# RT-HOT.net
KiCad netlist of a schematic drawn in Altium Designer
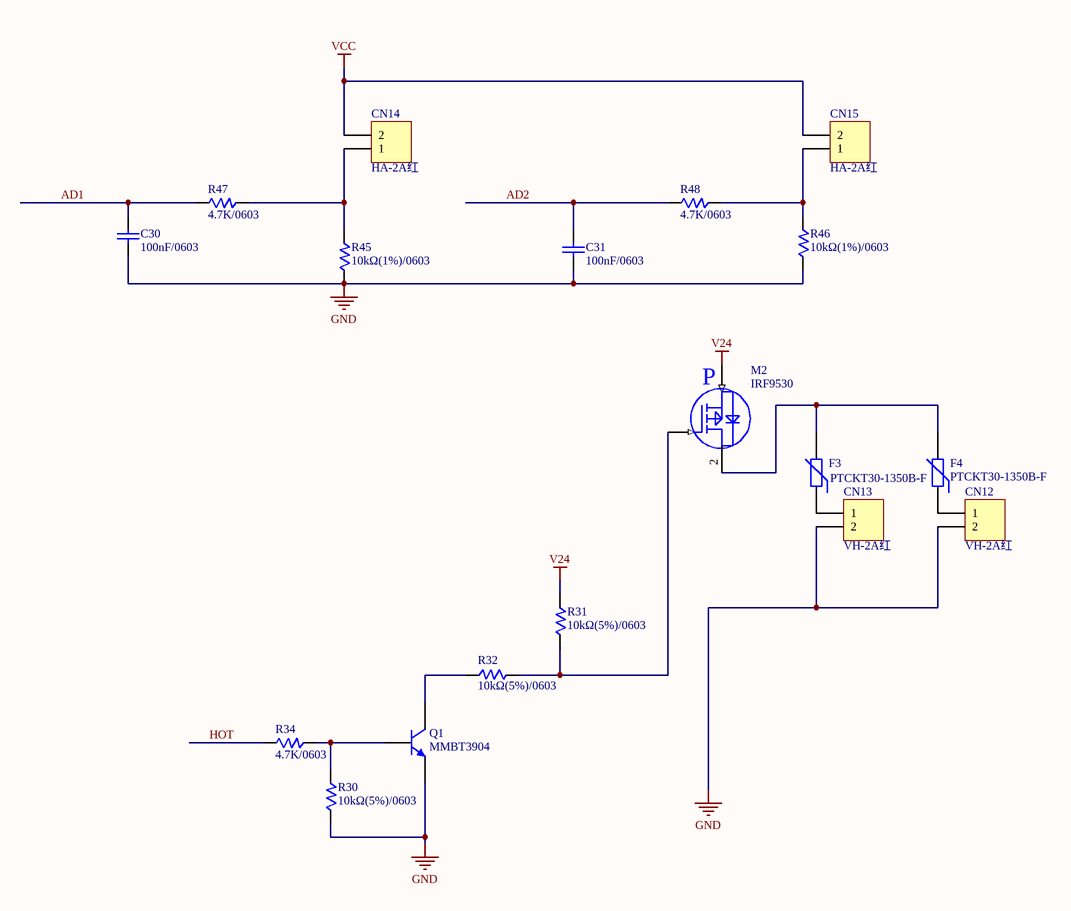
[diagram p0: RT-HOT.SchDoc]

(export (version "E")
  (design (tool "Eeschema 10.0.6"))
  (components
    (comp (ref "C30") (value "100nF/0603") (footprint "0603C") (libsource (lib "荣泰料号库") (part "C0603/100nF")))
    (comp (ref "C31") (value "100nF/0603") (footprint "0603C") (libsource (lib "荣泰料号库") (part "C0603/100nF")))
    (comp (ref "CN12")
      (value "VH-2A红")
      (footprint "CON-VH-2P")
      (libsource (lib "荣泰料号库") (part "CON-VH-2A(红色)"))
    )
    (comp (ref "CN13")
      (value "VH-2A红")
      (footprint "CON-VH-2P")
      (libsource (lib "荣泰料号库") (part "CON-VH-2A(红色)"))
    )
    (comp (ref "CN14")
      (value "HA-2A红")
      (footprint "CON-XA-2P")
      (libsource (lib "荣泰料号库") (part "CON-HA-2A(红色)"))
    )
    (comp (ref "CN15")
      (value "HA-2A红")
      (footprint "CON-XA-2P")
      (libsource (lib "荣泰料号库") (part "CON-HA-2A(红色)"))
    )
    (comp (ref "F3")
      (value "PTCKT30-1350B-F")
      (footprint "FRAD0.2")
      (libsource (lib "荣泰料号库") (part "F-PTCKT30-1350B-F/环保"))
    )
    (comp (ref "F4")
      (value "PTCKT30-1350B-F")
      (footprint "FRAD0.2")
      (libsource (lib "荣泰料号库") (part "F-PTCKT30-1350B-F/环保"))
    )
    (comp (ref "M2")
      (value "IRF9530")
      (footprint "TO-220AB")
      (libsource (lib "荣泰料号库") (part "MP-IRF9530/环保"))
    )
    (comp (ref "Q1")
      (value "MMBT3904")
      (footprint "SOT-23-N")
      (libsource (lib "荣泰料号库(5)") (part "Q-MMBT3904/1AM-N"))
    )
    (comp (ref "R30")
      (value "10kΩ(5%)/0603")
      (footprint "0603")
      (libsource (lib "荣泰料号库") (part "R0603/10kΩ/(5%)"))
    )
    (comp (ref "R31")
      (value "10kΩ(5%)/0603")
      (footprint "0603")
      (libsource (lib "荣泰料号库") (part "R0603/10kΩ/(5%)"))
    )
    (comp (ref "R32")
      (value "10kΩ(5%)/0603")
      (footprint "0603")
      (libsource (lib "荣泰料号库") (part "R0603/10kΩ/(5%)"))
    )
    (comp (ref "R34")
      (value "4.7K/0603")
      (footprint "0603")
      (libsource (lib "荣泰料号库") (part "R0603/4.7K/(5%)"))
    )
    (comp (ref "R45")
      (value "10kΩ(1%)/0603")
      (footprint "0603")
      (libsource (lib "荣泰料号库") (part "R0603/10kΩ(1%)"))
    )
    (comp (ref "R46")
      (value "10kΩ(1%)/0603")
      (footprint "0603")
      (libsource (lib "荣泰料号库") (part "R0603/10kΩ(1%)"))
    )
    (comp (ref "R47")
      (value "4.7K/0603")
      (footprint "0603")
      (libsource (lib "荣泰料号库") (part "R0603/4.7K/(5%)"))
    )
    (comp (ref "R48")
      (value "4.7K/0603")
      (footprint "0603")
      (libsource (lib "荣泰料号库") (part "R0603/4.7K/(5%)"))
    )
  )
  (nets
    (net (code "1") (name "/AD1") (class "Default")
      (node (ref "C30") (pin "1") (pinfunction "1_1") (pintype "passive"))
      (node (ref "R47") (pin "1") (pinfunction "1_1") (pintype "passive"))
    )
    (net (code "2") (name "/AD2") (class "Default")
      (node (ref "C31") (pin "1") (pinfunction "1_1") (pintype "passive"))
      (node (ref "R48") (pin "1") (pinfunction "1_1") (pintype "passive"))
    )
    (net (code "3") (name "/HOT") (class "Default")
      (node (ref "R34") (pin "1") (pinfunction "1_1") (pintype "passive"))
    )
    (net (code "4") (name "GND") (class "Default")
      (node (ref "C30") (pin "2") (pinfunction "2_2") (pintype "passive"))
      (node (ref "C31") (pin "2") (pinfunction "2_2") (pintype "passive"))
      (node (ref "CN12") (pin "2") (pinfunction "2_2") (pintype "passive"))
      (node (ref "CN13") (pin "2") (pinfunction "2_2") (pintype "passive"))
      (node (ref "Q1") (pin "E") (pinfunction "E_E") (pintype "passive"))
      (node (ref "R30") (pin "1") (pinfunction "1_1") (pintype "passive"))
      (node (ref "R45") (pin "1") (pinfunction "1_1") (pintype "passive"))
      (node (ref "R46") (pin "1") (pinfunction "1_1") (pintype "passive"))
    )
    (net (code "5") (name "Net-(CN12-Pad1)") (class "Default")
      (node (ref "CN12") (pin "1") (pinfunction "1_1") (pintype "passive"))
      (node (ref "F4") (pin "1") (pinfunction "1_1") (pintype "passive"))
    )
    (net (code "6") (name "Net-(CN13-Pad1)") (class "Default")
      (node (ref "CN13") (pin "1") (pinfunction "1_1") (pintype "passive"))
      (node (ref "F3") (pin "1") (pinfunction "1_1") (pintype "passive"))
    )
    (net (code "7") (name "Net-(CN14-Pad1)") (class "Default")
      (node (ref "CN14") (pin "1") (pinfunction "1_1") (pintype "passive"))
      (node (ref "R45") (pin "2") (pinfunction "2_2") (pintype "passive"))
      (node (ref "R47") (pin "2") (pinfunction "2_2") (pintype "passive"))
    )
    (net (code "8") (name "Net-(CN15-Pad1)") (class "Default")
      (node (ref "CN15") (pin "1") (pinfunction "1_1") (pintype "passive"))
      (node (ref "R46") (pin "2") (pinfunction "2_2") (pintype "passive"))
      (node (ref "R48") (pin "2") (pinfunction "2_2") (pintype "passive"))
    )
    (net (code "9") (name "Net-(M2-G)") (class "Default")
      (node (ref "M2") (pin "1") (pinfunction "G_1") (pintype "input"))
      (node (ref "R31") (pin "1") (pinfunction "1_1") (pintype "passive"))
      (node (ref "R32") (pin "1") (pinfunction "1_1") (pintype "passive"))
    )
    (net (code "10") (name "Net-(M2-S)") (class "Default")
      (node (ref "F3") (pin "2") (pinfunction "2_2") (pintype "passive"))
      (node (ref "F4") (pin "2") (pinfunction "2_2") (pintype "passive"))
      (node (ref "M2") (pin "2") (pinfunction "S_2") (pintype "passive"))
    )
    (net (code "11") (name "Net-(Q1-PadB)") (class "Default")
      (node (ref "Q1") (pin "B") (pinfunction "B_B") (pintype "passive"))
      (node (ref "R30") (pin "2") (pinfunction "2_2") (pintype "passive"))
      (node (ref "R34") (pin "2") (pinfunction "2_2") (pintype "passive"))
    )
    (net (code "12") (name "Net-(Q1-PadC)") (class "Default")
      (node (ref "Q1") (pin "C") (pinfunction "C_C") (pintype "passive"))
      (node (ref "R32") (pin "2") (pinfunction "2_2") (pintype "passive"))
    )
    (net (code "13") (name "V24") (class "Default")
      (node (ref "M2") (pin "3") (pinfunction "D_3") (pintype "input"))
      (node (ref "R31") (pin "2") (pinfunction "2_2") (pintype "passive"))
    )
    (net (code "14") (name "VCC") (class "Default")
      (node (ref "CN14") (pin "2") (pinfunction "2_2") (pintype "passive"))
      (node (ref "CN15") (pin "2") (pinfunction "2_2") (pintype "passive"))
    )
  )
)
